# tps63020-buck-boost-flashlight-driver-te.net
KiCad netlist of a schematic drawn in EAGLE
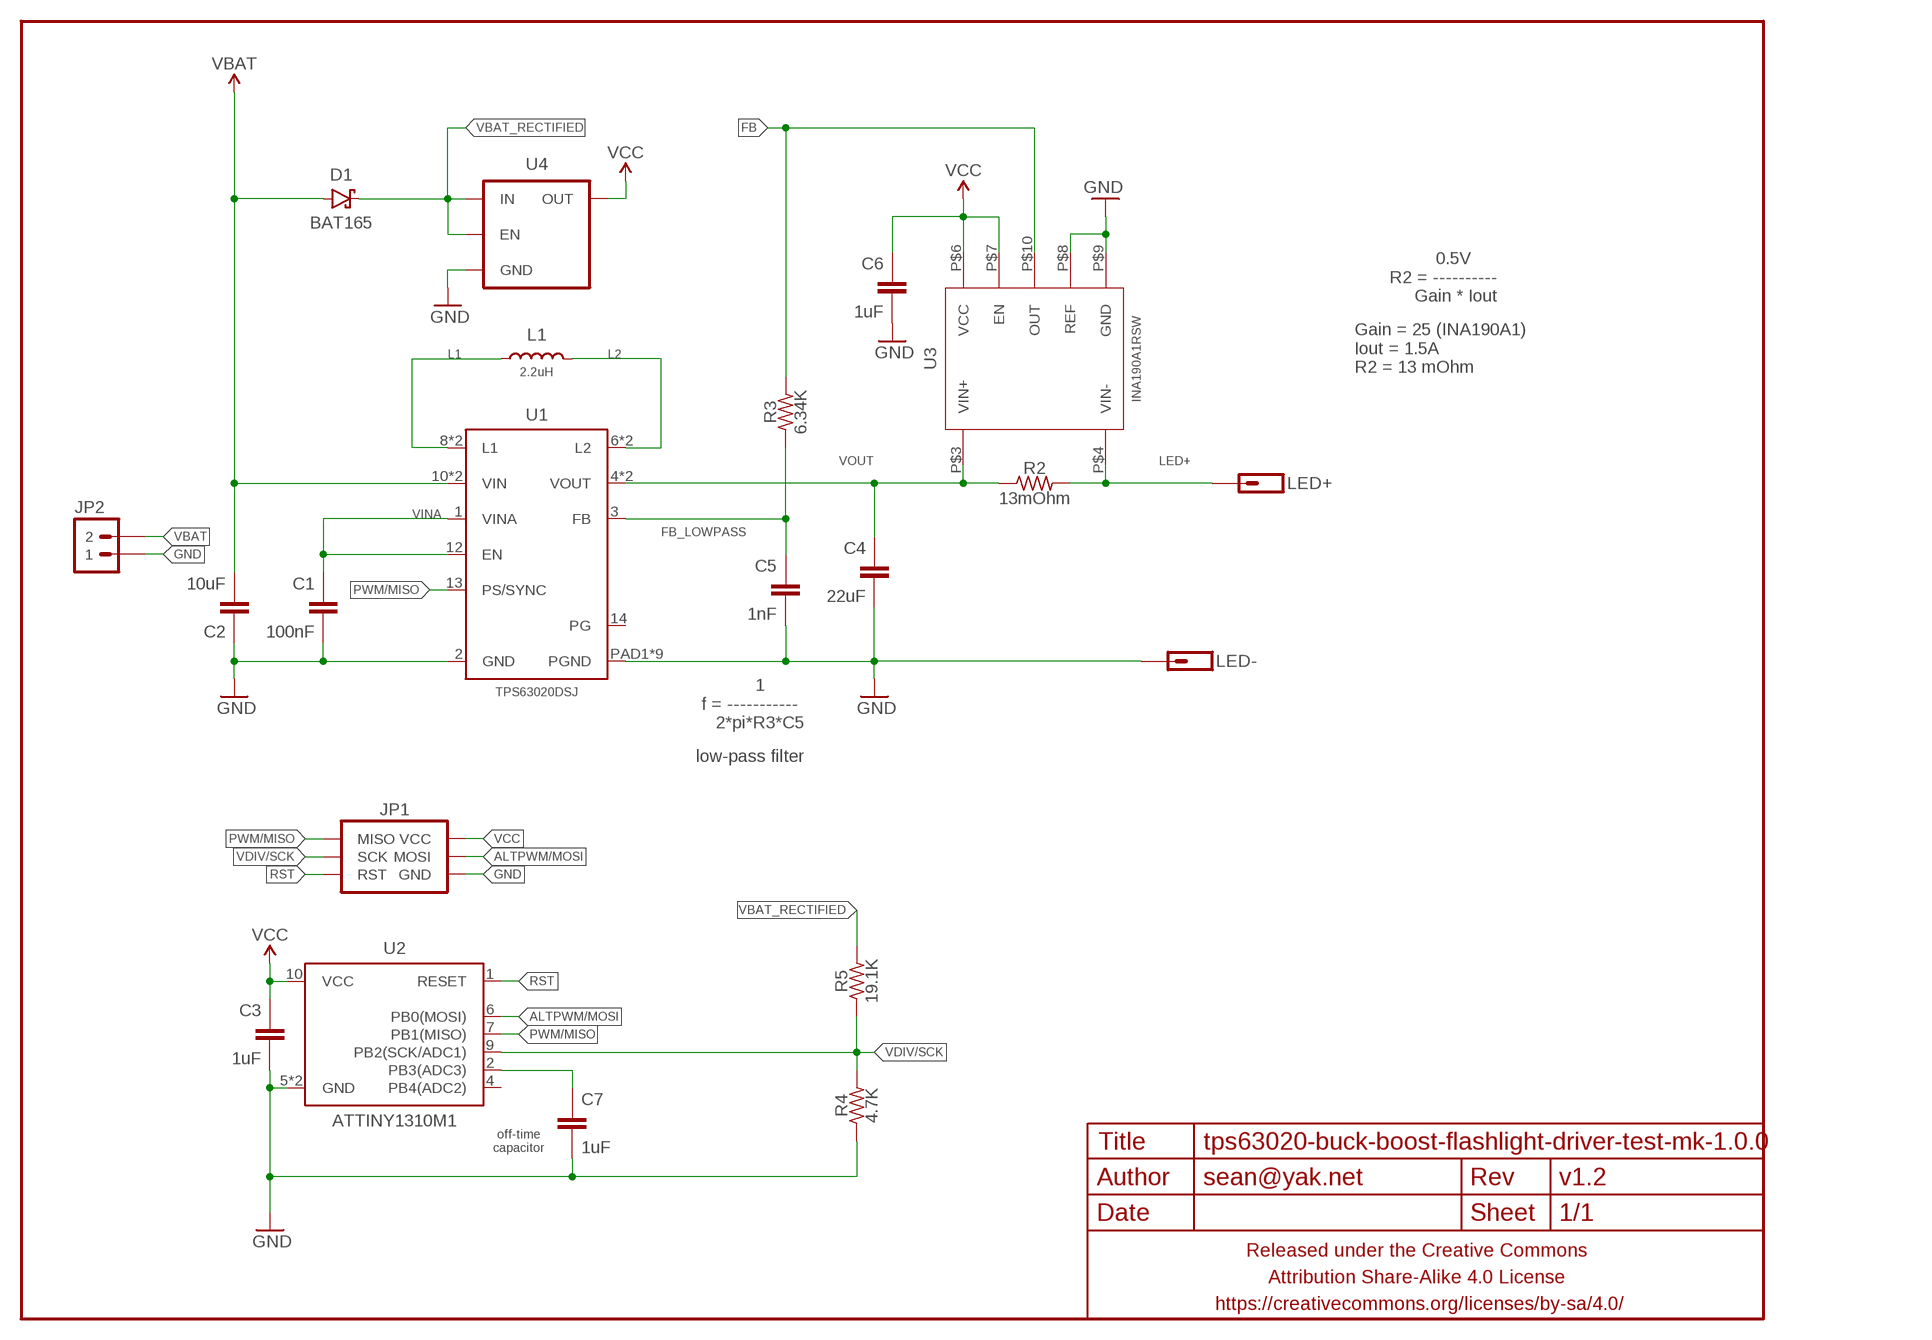
[diagram p0: schematic, sheet 1]

(export (version "E")
  (design (tool "Eeschema 10.0.6"))
  (components
    (comp (ref "C1")
      (value "100nF")
      (footprint "eagle-import:C0402")
      (libsource (lib "eagle-import") (part "CAPACITOR-CERAMICC0402"))
    )
    (comp (ref "C2")
      (value "10uF")
      (footprint "eagle-import:C0805-TIGHTER")
      (libsource (lib "eagle-import") (part "CAPACITOR-CERAMICC0805-TIGHTER"))
    )
    (comp (ref "C3")
      (value "1uF")
      (footprint "eagle-import:C0402")
      (libsource (lib "eagle-import") (part "CAPACITOR-CERAMICC0402"))
    )
    (comp (ref "C4")
      (value "22uF")
      (footprint "eagle-import:C0805-TIGHTER")
      (libsource (lib "eagle-import") (part "CAPACITOR-CERAMICC0805-TIGHTER"))
    )
    (comp (ref "C5")
      (value "1nF")
      (footprint "eagle-import:C0402")
      (libsource (lib "eagle-import") (part "CAPACITOR-CERAMICC0402"))
    )
    (comp (ref "C6")
      (value "1uF")
      (footprint "eagle-import:C0402")
      (libsource (lib "eagle-import") (part "CAPACITOR-CERAMICC0402"))
    )
    (comp (ref "C7")
      (value "1uF")
      (footprint "eagle-import:C0402")
      (libsource (lib "eagle-import") (part "CAPACITOR-CERAMICC0402"))
    )
    (comp (ref "D1")
      (value "BAT165")
      (footprint "eagle-import:SOD323-SCHOTTKY")
      (libsource (lib "eagle-import") (part "DIODE-SCHOTTKYSOD323"))
    )
    (comp (ref "FRAME1")
      (value "FRAME-LETTERNO_PACKAGE")
      (footprint "eagle-import:DUMMY")
      (fields
        (field (name "DESIGNER") "sean@yak.net")
        (field (name "VERSION") "v1.2")
        (field (name "DESIGNER_1") "sean@yak.net")
        (field (name "VERSION_1") "v1.2")
      )
      (libsource (lib "eagle-import") (part "FRAME-LETTERNO_PACKAGE"))
    )
    (comp (ref "JP1")
      (value "AVR_SPI_PRG_6PTH-1.27MM")
      (footprint "eagle-import:2X3-1.27MM-PTH")
      (libsource (lib "eagle-import") (part "AVR_SPI_PRG_6PTH-1.27MM"))
    )
    (comp (ref "JP2")
      (value "M02PTH-2MM")
      (footprint "eagle-import:1X02-2MM-PTH")
      (libsource (lib "eagle-import") (part "M02PTH-2MM"))
    )
    (comp (ref "L1")
      (value "2.2uH")
      (footprint "eagle-import:XAL50X0")
      (libsource (lib "eagle-import") (part "INDUCTORXAL50X0"))
    )
    (comp (ref "LED+")
      (value "M01PTH-1MM-CIR-NS")
      (footprint "eagle-import:1X01-1MM-CIR-NS")
      (libsource (lib "eagle-import") (part "M01PTH-1MM-CIR-NS"))
    )
    (comp (ref "LED-")
      (value "M01PTH-1MM-CIR-NS")
      (footprint "eagle-import:1X01-1MM-CIR-NS")
      (libsource (lib "eagle-import") (part "M01PTH-1MM-CIR-NS"))
    )
    (comp (ref "R2")
      (value "13mOhm")
      (footprint "eagle-import:R0805-TIGHTER")
      (libsource (lib "eagle-import") (part "RESISTORR0805-TIGHTER"))
    )
    (comp (ref "R3")
      (value "6.34K")
      (footprint "eagle-import:R0402")
      (libsource (lib "eagle-import") (part "RESISTORR0402"))
    )
    (comp (ref "R4")
      (value "4.7K")
      (footprint "eagle-import:R0402")
      (libsource (lib "eagle-import") (part "RESISTORR0402"))
    )
    (comp (ref "R5")
      (value "19.1K")
      (footprint "eagle-import:R0402")
      (libsource (lib "eagle-import") (part "RESISTORR0402"))
    )
    (comp (ref "U1")
      (value "TPS63020DSJ")
      (footprint "eagle-import:VSON-14-4MMX3MM")
      (libsource (lib "eagle-import") (part "TPS63020DSJ"))
    )
    (comp (ref "U2")
      (value "ATTINY1310M1")
      (footprint "eagle-import:QFN10(2X5)")
      (libsource (lib "eagle-import") (part "ATTINY1310M1"))
    )
    (comp (ref "U3")
      (value "INA190A1RSW")
      (footprint "eagle-import:UQFN-10")
      (libsource (lib "eagle-import") (part "INA190RSW"))
    )
    (comp (ref "U4")
      (value "V_REG_ENTLV700")
      (footprint "eagle-import:SC70")
      (libsource (lib "eagle-import") (part "V_REG_ENTLV700"))
    )
  )
  (nets
    (net (code "1") (name "/FB_LOWPASS") (class "Default")
      (node (ref "C5") (pin "1") (pinfunction "1_1") (pintype "passive"))
      (node (ref "R3") (pin "1") (pinfunction "1_1") (pintype "passive"))
      (node (ref "U1") (pin "3") (pinfunction "FB_3") (pintype "bidirectional"))
    )
    (net (code "2") (name "/L1") (class "Default")
      (node (ref "L1") (pin "P$1") (pinfunction "1_P$1") (pintype "passive"))
      (node (ref "U1") (pin "8") (pinfunction "L1_8") (pintype "bidirectional"))
      (node (ref "U1") (pin "9") (pinfunction "L1_9") (pintype "bidirectional"))
    )
    (net (code "3") (name "/L2") (class "Default")
      (node (ref "L1") (pin "P$2") (pinfunction "2_P$2") (pintype "passive"))
      (node (ref "U1") (pin "6") (pinfunction "L2_6") (pintype "bidirectional"))
      (node (ref "U1") (pin "7") (pinfunction "L2_7") (pintype "bidirectional"))
    )
    (net (code "4") (name "/LED+") (class "Default")
      (node (ref "LED+") (pin "1") (pinfunction "1_1") (pintype "passive"))
      (node (ref "R2") (pin "2") (pinfunction "2_2") (pintype "passive"))
      (node (ref "U3") (pin "P$4") (pinfunction "VIN-_P$4") (pintype "bidirectional"))
    )
    (net (code "5") (name "/VINA") (class "Default")
      (node (ref "C1") (pin "1") (pinfunction "1_1") (pintype "passive"))
      (node (ref "U1") (pin "1") (pinfunction "VINA_1") (pintype "bidirectional"))
      (node (ref "U1") (pin "12") (pinfunction "EN_12") (pintype "bidirectional"))
    )
    (net (code "6") (name "/VOUT") (class "Default")
      (node (ref "C4") (pin "1") (pinfunction "1_1") (pintype "passive"))
      (node (ref "R2") (pin "1") (pinfunction "1_1") (pintype "passive"))
      (node (ref "U1") (pin "4") (pinfunction "VOUT_4") (pintype "bidirectional"))
      (node (ref "U1") (pin "5") (pinfunction "VOUT_5") (pintype "bidirectional"))
      (node (ref "U3") (pin "P$3") (pinfunction "VIN+_P$3") (pintype "bidirectional"))
    )
    (net (code "7") (name "ALTPWM{slash}MOSI") (class "Default")
      (node (ref "JP1") (pin "4") (pinfunction "MOSI_4") (pintype "passive"))
      (node (ref "U2") (pin "6") (pinfunction "PB0(MOSI)_6") (pintype "bidirectional"))
    )
    (net (code "8") (name "FB") (class "Default")
      (node (ref "R3") (pin "2") (pinfunction "2_2") (pintype "passive"))
      (node (ref "U3") (pin "P$10") (pinfunction "OUT_P$10") (pintype "bidirectional"))
    )
    (net (code "9") (name "GND") (class "Default")
      (node (ref "C1") (pin "2") (pinfunction "2_2") (pintype "passive"))
      (node (ref "C2") (pin "1") (pinfunction "1_1") (pintype "passive"))
      (node (ref "C3") (pin "2") (pinfunction "2_2") (pintype "passive"))
      (node (ref "C4") (pin "2") (pinfunction "2_2") (pintype "passive"))
      (node (ref "C5") (pin "2") (pinfunction "2_2") (pintype "passive"))
      (node (ref "C6") (pin "2") (pinfunction "2_2") (pintype "passive"))
      (node (ref "C7") (pin "2") (pinfunction "2_2") (pintype "passive"))
      (node (ref "JP1") (pin "6") (pinfunction "GND_6") (pintype "passive"))
      (node (ref "JP2") (pin "P$1") (pinfunction "1_P$1") (pintype "passive"))
      (node (ref "LED-") (pin "1") (pinfunction "1_1") (pintype "passive"))
      (node (ref "R4") (pin "1") (pinfunction "1_1") (pintype "passive"))
      (node (ref "U1") (pin "2") (pinfunction "GND_2") (pintype "bidirectional"))
      (node (ref "U1") (pin "PAD1") (pinfunction "PGND_PAD1") (pintype "bidirectional"))
      (node (ref "U1") (pin "PAD2") (pinfunction "PGND_PAD2") (pintype "bidirectional"))
      (node (ref "U1") (pin "PAD3") (pinfunction "PGND_PAD3") (pintype "bidirectional"))
      (node (ref "U1") (pin "PAD4") (pinfunction "PGND_PAD4") (pintype "bidirectional"))
      (node (ref "U1") (pin "PAD5") (pinfunction "PGND_PAD5") (pintype "bidirectional"))
      (node (ref "U1") (pin "PAD6") (pinfunction "PGND_PAD6") (pintype "bidirectional"))
      (node (ref "U1") (pin "PAD7") (pinfunction "PGND_PAD7") (pintype "bidirectional"))
      (node (ref "U1") (pin "PAD8") (pinfunction "PGND_PAD8") (pintype "bidirectional"))
      (node (ref "U1") (pin "PADCENTER") (pinfunction "PGND_PADCENTER") (pintype "bidirectional"))
      (node (ref "U2") (pin "5") (pinfunction "GND_5") (pintype "bidirectional"))
      (node (ref "U2") (pin "PAD") (pinfunction "GND_PAD") (pintype "bidirectional"))
      (node (ref "U3") (pin "P$8") (pinfunction "REF_P$8") (pintype "bidirectional"))
      (node (ref "U3") (pin "P$9") (pinfunction "GND_P$9") (pintype "bidirectional"))
      (node (ref "U4") (pin "2") (pinfunction "GND_2") (pintype "input"))
    )
    (net (code "10") (name "Net-(U2-PB3(ADC3))") (class "Default")
      (node (ref "C7") (pin "1") (pinfunction "1_1") (pintype "passive"))
      (node (ref "U2") (pin "2") (pinfunction "PB3(ADC3)_2") (pintype "bidirectional"))
    )
    (net (code "11") (name "PWM{slash}MISO") (class "Default")
      (node (ref "JP1") (pin "1") (pinfunction "MISO_1") (pintype "passive"))
      (node (ref "U1") (pin "13") (pinfunction "PS/SYNC_13") (pintype "bidirectional"))
      (node (ref "U2") (pin "7") (pinfunction "PB1(MISO)_7") (pintype "bidirectional"))
    )
    (net (code "12") (name "RST") (class "Default")
      (node (ref "JP1") (pin "5") (pinfunction "RST_5") (pintype "passive"))
      (node (ref "U2") (pin "1") (pinfunction "RESET_1") (pintype "bidirectional"))
    )
    (net (code "13") (name "VBAT") (class "Default")
      (node (ref "C2") (pin "2") (pinfunction "2_2") (pintype "passive"))
      (node (ref "D1") (pin "A") (pinfunction "A_A") (pintype "passive"))
      (node (ref "JP2") (pin "P$2") (pinfunction "2_P$2") (pintype "passive"))
      (node (ref "U1") (pin "10") (pinfunction "VIN_10") (pintype "bidirectional"))
      (node (ref "U1") (pin "11") (pinfunction "VIN_11") (pintype "bidirectional"))
    )
    (net (code "14") (name "VBAT_RECTIFIED") (class "Default")
      (node (ref "D1") (pin "C") (pinfunction "C_C") (pintype "passive"))
      (node (ref "R5") (pin "2") (pinfunction "2_2") (pintype "passive"))
      (node (ref "U4") (pin "1") (pinfunction "IN_1") (pintype "input"))
      (node (ref "U4") (pin "3") (pinfunction "EN_3") (pintype "input"))
    )
    (net (code "15") (name "VCC") (class "Default")
      (node (ref "C3") (pin "1") (pinfunction "1_1") (pintype "passive"))
      (node (ref "C6") (pin "1") (pinfunction "1_1") (pintype "passive"))
      (node (ref "JP1") (pin "2") (pinfunction "VCC_2") (pintype "passive"))
      (node (ref "U2") (pin "10") (pinfunction "VCC_10") (pintype "bidirectional"))
      (node (ref "U3") (pin "P$6") (pinfunction "VCC_P$6") (pintype "bidirectional"))
      (node (ref "U3") (pin "P$7") (pinfunction "EN_P$7") (pintype "bidirectional"))
      (node (ref "U4") (pin "5") (pinfunction "OUT_5") (pintype "passive"))
    )
    (net (code "16") (name "VDIV{slash}SCK") (class "Default")
      (node (ref "JP1") (pin "3") (pinfunction "SCK_3") (pintype "passive"))
      (node (ref "R4") (pin "2") (pinfunction "2_2") (pintype "passive"))
      (node (ref "R5") (pin "1") (pinfunction "1_1") (pintype "passive"))
      (node (ref "U2") (pin "9") (pinfunction "PB2(SCK/ADC1)_9") (pintype "bidirectional"))
    )
    (net (code "17") (name "unconnected-(U1-PG-Pad14)") (class "Default")
      (node (ref "U1") (pin "14") (pinfunction "PG_14") (pintype "bidirectional"))
    )
    (net (code "18") (name "unconnected-(U2-PB4(ADC2)-Pad4)") (class "Default")
      (node (ref "U2") (pin "4") (pinfunction "PB4(ADC2)_4") (pintype "bidirectional"))
    )
  )
)
